# DRV8353FH_v0_7_Schematic.net
KiCad netlist of a schematic drawn in Altium Designer
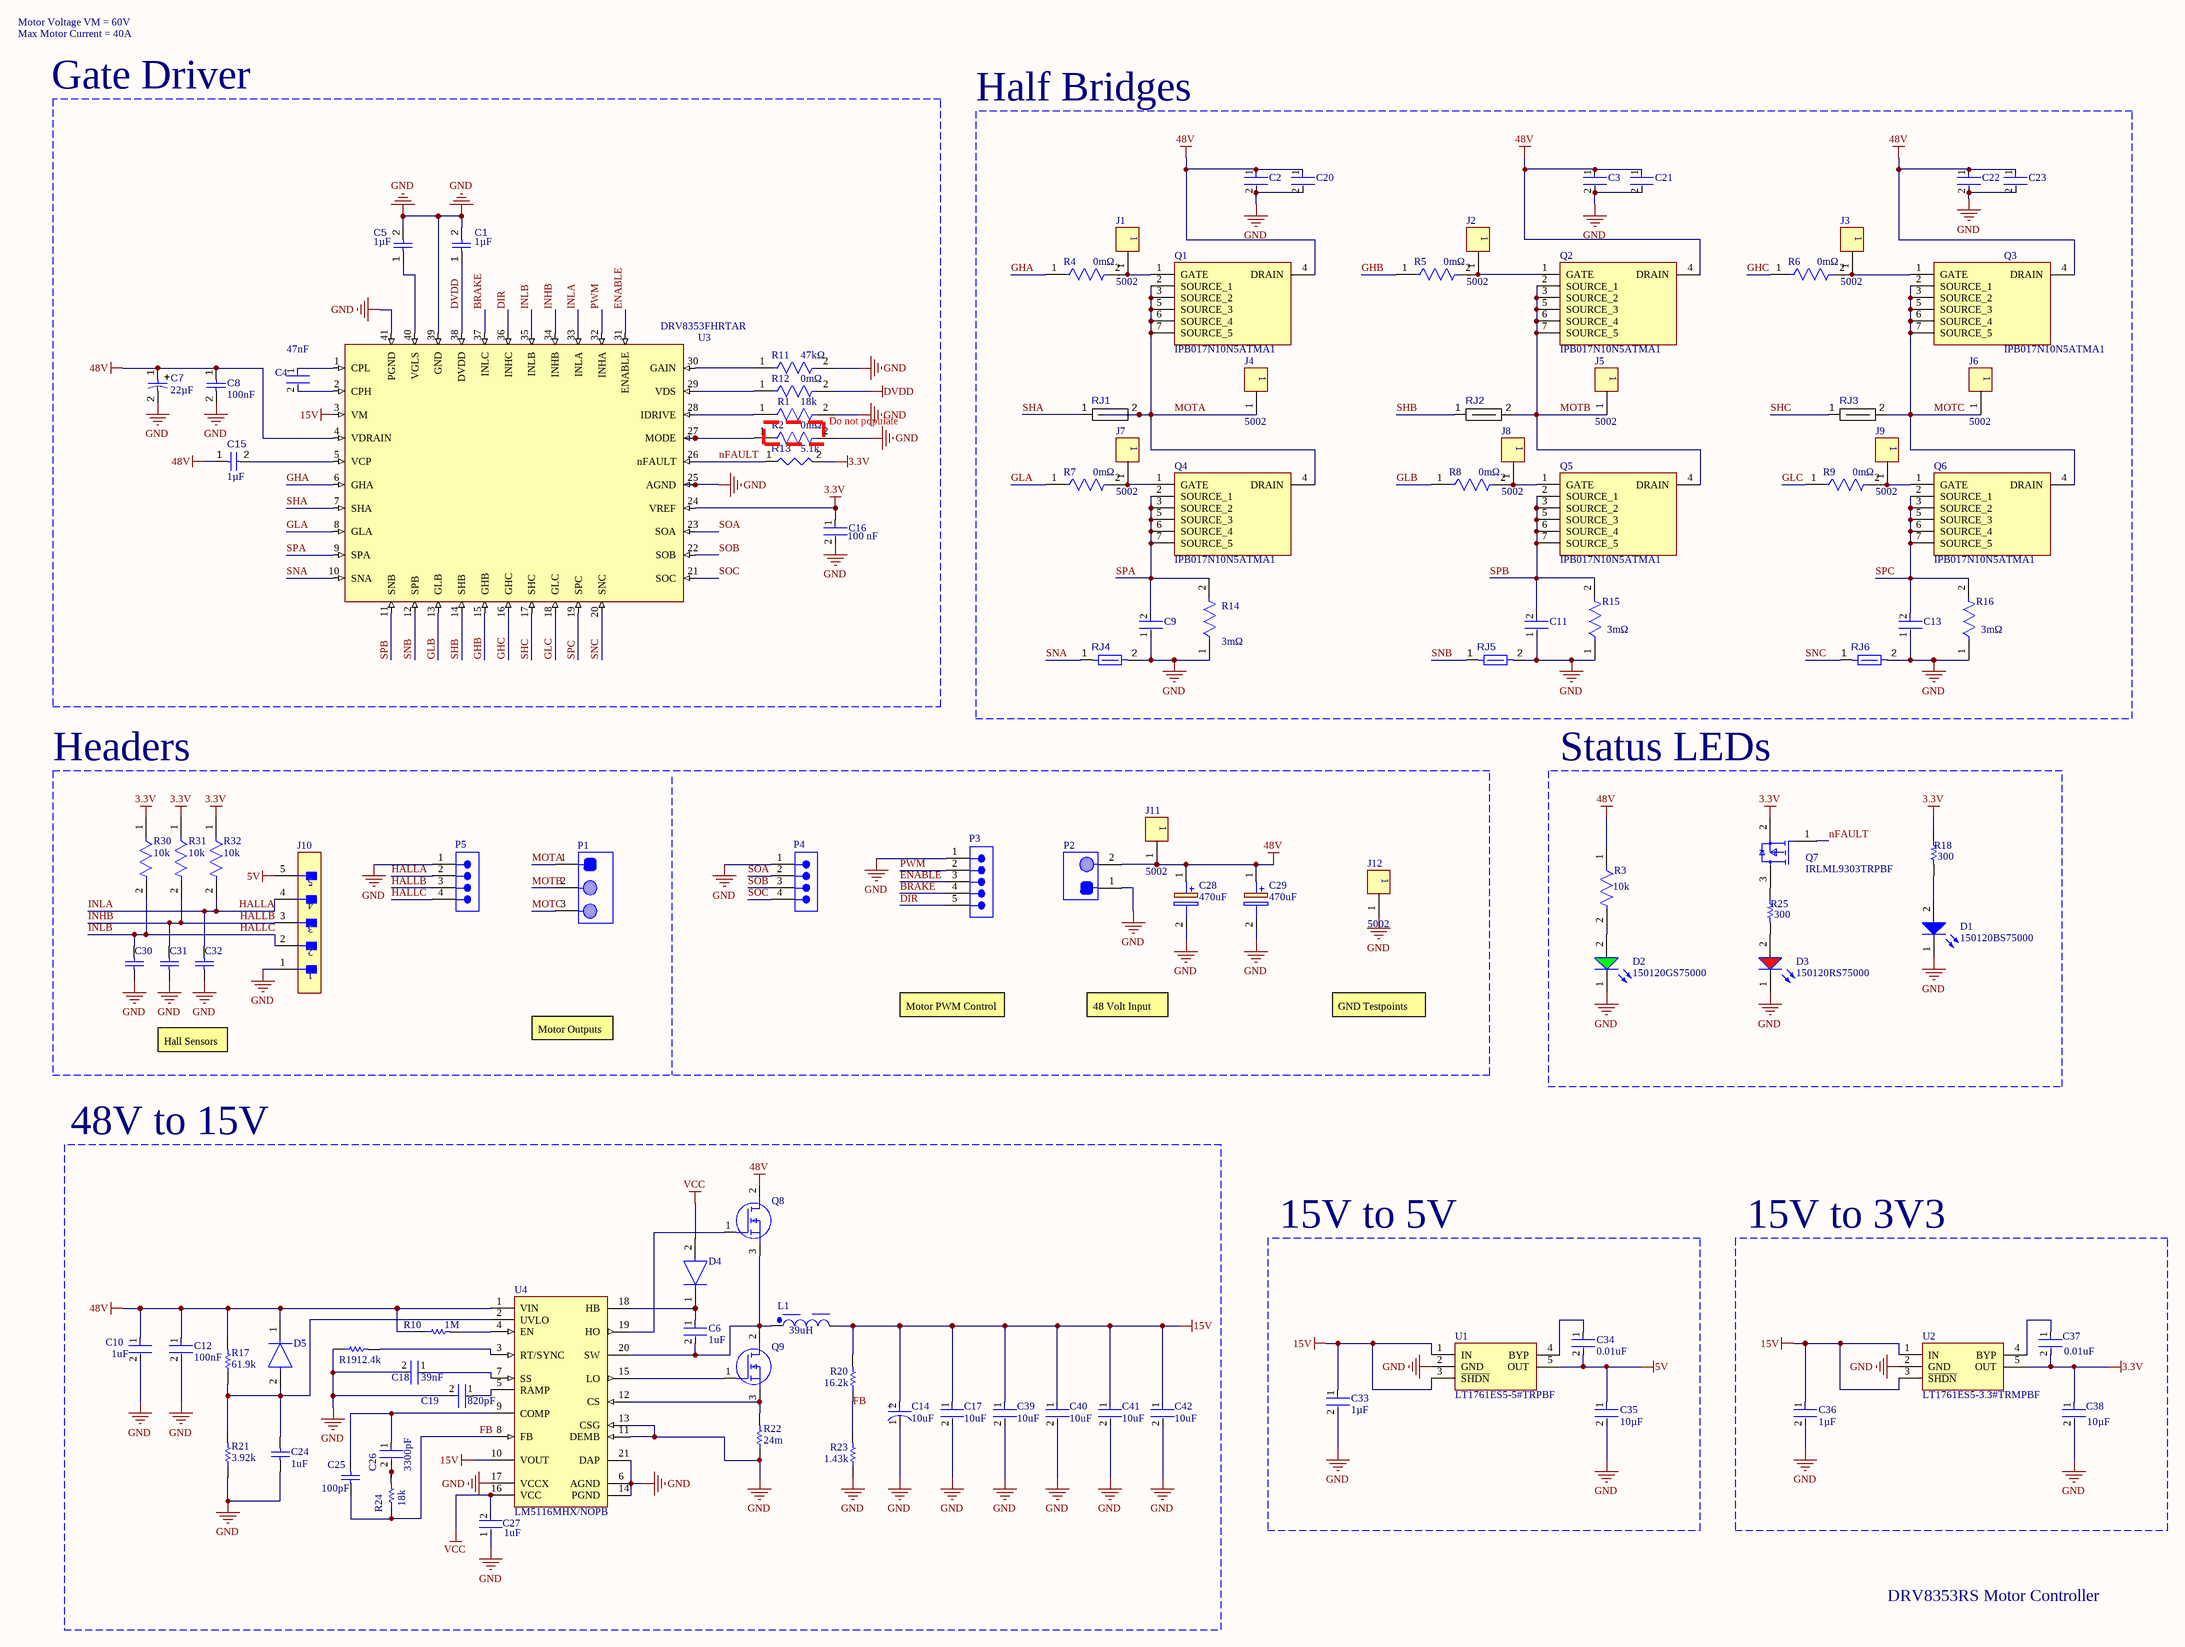
[diagram p0: DRV8353FH_v0.7_Schematic.SchDoc]

(export (version "E")
  (design (tool "Eeschema 10.0.6"))
  (components
    (comp (ref "C1")
      (value "1µF")
      (footprint "FP-CC0603-DA-IPC_B")
      (fields (field (name "Comment") "CC0603KRX5R8BB105"))
      (libsource (lib "CEV Electrical") (part "CAP-NP-2"))
    )
    (comp (ref "C2")
      (value "C1210C105K1RACTU")
      (footprint "FP-C1210C105K1RACTU-MFG")
      (description "CAP CER 1UF 100V X7R 1210")
      (fields (field (name "VOLTAGE") "100V") (field (name "TOLERANCE") "10%"))
      (libsource (lib "Altium Content Vault") (part "b4654b650e69147ec39a6b967a45e02"))
    )
    (comp (ref "C3")
      (value "C1210C105K1RACTU")
      (footprint "FP-C1210C105K1RACTU-MFG")
      (description "CAP CER 1UF 100V X7R 1210")
      (fields (field (name "VOLTAGE") "100V") (field (name "TOLERANCE") "10%"))
      (libsource (lib "Altium Content Vault") (part "b4654b650e69147ec39a6b967a45e02"))
    )
    (comp (ref "C4")
      (value "GCJ21BR72A473KA01L")
      (footprint "FP-GCJ21B-0_3-MFG")
      (description "Multilayer Ceramic Capacitors MLCC - SMD/SMT 0805 47000pF 10%, 100VDC,  X7R 15%")
      (fields (field (name "CAPACITANCE") "47nF") (field (name "TOLERANCE") "10%"))
      (libsource (lib "Altium Content Vault") (part "02cd4be3c70576c341d710602a673aa"))
    )
    (comp (ref "C5")
      (value "1µF")
      (footprint "FP-CC0603-DA-IPC_B")
      (fields (field (name "Comment") "CC0603KRX5R8BB105"))
      (libsource (lib "CEV Electrical") (part "CAP-NP-2"))
    )
    (comp (ref "C6")
      (value "1uF")
      (footprint "FP-CC0603-DA-MFG")
      (description "CAP CER 1UF 25V X5R 0603")
      (fields
        (field (name "OCTOPART") "https://octopart.com/cc0603krx5r8bb105-yageo-9292811")
        (field (name "MANUFACTURER") "YAGEO")
      )
      (libsource (lib "Altium Content Vault") (part "11868f565c42a9108669ba33697ecf6"))
    )
    (comp (ref "C7")
      (value "22µF")
      (footprint "CAPAE8983X105N")
      (fields (field (name "Comment") "UCD2A220MNL1GS"))
      (libsource (lib "") (part "CAP-NP-2_1"))
    )
    (comp (ref "C8")
      (value "100nF")
      (footprint "FP-CL10-IPC_B")
      (fields (field (name "Comment") "CL10B104KC8NNNC"))
      (libsource (lib "CEV Electrical") (part "CAP-NP-2"))
    )
    (comp (ref "C9")
      (value "C1608C0G2A102J080AA")
      (footprint "FP-C1608-080-0_1-MFG")
      (description "Multilayer Ceramic Capacitors 1nF ±5% 100V C0G SMD 0603")
      (fields (field (name "TOLERANCE") "5%"))
      (libsource (lib "Altium Content Vault") (part "236180d848d6139a670b325ea6854c9"))
    )
    (comp (ref "C10")
      (value "1uF")
      (footprint "FP-CL32-IPC_C")
      (description "Cap Ceramic 1uF 100V X7R ±10% SMD 1210 +125°C Embossed T/R")
      (fields (field (name "TOLERANCE") "10%") (field (name "VOLTAGE") "100V"))
      (libsource (lib "Altium Content Vault") (part "b4654b650e69147ec39a6b967a45e02"))
    )
    (comp (ref "C11")
      (value "C1608C0G2A102J080AA")
      (footprint "FP-C1608-080-0_1-MFG")
      (description "Multilayer Ceramic Capacitors 1nF ±5% 100V C0G SMD 0603")
      (fields (field (name "TOLERANCE") "5%"))
      (libsource (lib "Altium Content Vault") (part "236180d848d6139a670b325ea6854c9"))
    )
    (comp (ref "C12")
      (value "100nF")
      (footprint "FP-GRM188-0_1-e0_2_0_5-IPC_B")
      (description "Chip Multilayer Ceramic Capacitors for General Purpose, 0603, 0.10uF, X7R, 15%, 10%, 100V")
      (fields (field (name "VOLTAGE") "100V") (field (name "TOLERANCE") "10%"))
      (libsource (lib "Altium Content Vault") (part "11868f565c42a9108669ba33697ecf6"))
    )
    (comp (ref "C13")
      (value "C1608C0G2A102J080AA")
      (footprint "FP-C1608-080-0_1-MFG")
      (description "Multilayer Ceramic Capacitors 1nF ±5% 100V C0G SMD 0603")
      (fields (field (name "TOLERANCE") "5%"))
      (libsource (lib "Altium Content Vault") (part "236180d848d6139a670b325ea6854c9"))
    )
    (comp (ref "C14")
      (value "10uF")
      (footprint "FP-OS-CON-SMT-C6-MFG")
      (description "Conductive Polymer Aluminum Solid Capacitors (OS-CON) 10uF ±20% 50V")
      (fields (field (name "VOLTAGE") "50V") (field (name "TOLERANCE") "20%"))
      (libsource (lib "Altium Content Vault") (part "a00bbbee19879c290e62620ae7e47b1"))
    )
    (comp (ref "C15")
      (value "1µF")
      (footprint "FP-CC0603-DA-IPC_B")
      (fields (field (name "Comment") "CC0603KRX5R8BB105"))
      (libsource (lib "CEV Electrical") (part "CAP-NP-2"))
    )
    (comp (ref "C16")
      (value "100 nF")
      (footprint "FP-CC0603-DA-MFG")
      (description "CAP CER 0.1UF 16V X7R 0603")
      (fields
        (field (name "OCTOPART") "https://octopart.com/cc0603krx7r7bb104-yageo-192941")
        (field (name "TOLERANCE") "0.1")
      )
      (libsource (lib "Altium Content Vault") (part "11868f565c42a9108669ba33697ecf6"))
    )
    (comp (ref "C17")
      (value "10uF")
      (footprint "FP-CL31-IPC_C")
      (description "CAP CER 10UF 50V X5R 1206")
      (fields (field (name "TOLERANCE") "10%") (field (name "MANUFACTURER") "Samsung"))
      (libsource (lib "Altium Content Vault") (part "11868f565c42a9108669ba33697ecf6"))
    )
    (comp (ref "C18")
      (value "39nF")
      (footprint "FP-C0805C-DN-MFG")
      (description "C0805 39,000 pF U2J 30ppm/°C 1.00% 50 V")
      (fields
        (field (name "MANUFACTURER PART NUMBER") "C0805C393F5JACAUTO")
        (field (name "TOLERANCE") "0.01")
      )
      (libsource (lib "Altium Content Vault") (part "b4654b650e69147ec39a6b967a45e02"))
    )
    (comp (ref "C19")
      (value "820pF")
      (footprint "FP-C1608-080-0_1-IPC_C")
      (description "Multilayer Ceramic Capacitors 820pF ±5% 50V C0G SMD 0603")
      (fields (field (name "TOLERANCE") "5%"))
      (libsource (lib "Altium Content Vault") (part "236180d848d6139a670b325ea6854c9"))
    )
    (comp (ref "C20")
      (value "C1210C105K1RACTU")
      (footprint "FP-C1210C105K1RACTU-MFG")
      (description "CAP CER 1UF 100V X7R 1210")
      (fields (field (name "VOLTAGE") "100V") (field (name "TOLERANCE") "10%"))
      (libsource (lib "Altium Content Vault") (part "b4654b650e69147ec39a6b967a45e02"))
    )
    (comp (ref "C21")
      (value "C1210C105K1RACTU")
      (footprint "FP-C1210C105K1RACTU-MFG")
      (description "CAP CER 1UF 100V X7R 1210")
      (fields (field (name "VOLTAGE") "100V") (field (name "TOLERANCE") "10%"))
      (libsource (lib "Altium Content Vault") (part "b4654b650e69147ec39a6b967a45e02"))
    )
    (comp (ref "C22")
      (value "C1210C105K1RACTU")
      (footprint "FP-C1210C105K1RACTU-MFG")
      (description "CAP CER 1UF 100V X7R 1210")
      (fields (field (name "VOLTAGE") "100V") (field (name "TOLERANCE") "10%"))
      (libsource (lib "Altium Content Vault") (part "b4654b650e69147ec39a6b967a45e02"))
    )
    (comp (ref "C23")
      (value "C1210C105K1RACTU")
      (footprint "FP-C1210C105K1RACTU-MFG")
      (description "CAP CER 1UF 100V X7R 1210")
      (fields (field (name "VOLTAGE") "100V") (field (name "TOLERANCE") "10%"))
      (libsource (lib "Altium Content Vault") (part "b4654b650e69147ec39a6b967a45e02"))
    )
    (comp (ref "C24")
      (value "1uF")
      (footprint "CAPC2013X140X50ML20T25")
      (fields (field (name "MANUFACTURER") "Kemet") (field (name "PART NUMBER") "C0805C105K5RACTU"))
      (libsource (lib "Altium Content Vault") (part "CAP"))
    )
    (comp (ref "C25")
      (value "100pF")
      (footprint "CAPC1608X90X40ML10T20")
      (description "Chip Capacitor, 100 pF, +/- 5%, 50 V, -55 to 125 degC, 0603 (1608 Metric), RoHS, Tape and Reel")
      (fields (field (name "TOLERANCE") "5%") (field (name "VOLTAGE") "50V"))
      (libsource (lib "Altium Content Vault") (part "CAP-NP-2"))
    )
    (comp (ref "C26")
      (value "3300pF")
      (footprint "FP-C0603C-CF-MFG")
      (description "CAP CER 3300PF 50V 5% X7R 0603")
      (fields
        (field (name "MANUFACTURER PART NUMBER") "C0603C332J5RACTU")
        (field (name "MANUFACTURER") "KEMET")
      )
      (libsource (lib "Altium Content Vault") (part "b4654b650e69147ec39a6b967a45e02"))
    )
    (comp (ref "C27")
      (value "1uF")
      (footprint "FP-C1608-080-0_1-MFG")
      (description "Multilayer Ceramic Capacitors 1μF ±10% 35V X7R SMD 0603")
      (fields (field (name "TOLERANCE") "10%"))
      (libsource (lib "Altium Content Vault") (part "236180d848d6139a670b325ea6854c9"))
    )
    (comp (ref "C28")
      (value "470uF")
      (footprint "SamacSys:CAPPRD750W85D1800H4200")
      (description "Capacitor Polarised")
      (fields
        (field (name "MANUFACTURER_PART_NUMBER") "ECA-2CM471")
        (field (name "MOUSER PART NUMBER") "667-ECA-2CM471")
      )
      (libsource (lib "*") (part "ECA-2CM471"))
    )
    (comp (ref "C29")
      (value "470uF")
      (footprint "SamacSys:CAPPRD750W85D1800H4200")
      (description "Capacitor Polarised")
      (fields
        (field (name "MANUFACTURER_PART_NUMBER") "ECA-2CM471")
        (field (name "MOUSER PART NUMBER") "667-ECA-2CM471")
      )
      (libsource (lib "*") (part "ECA-2CM471"))
    )
    (comp (ref "C30")
      (value "VJ0603Y102KXACW1BC")
      (footprint "CAPC1608X95X40NL15T15")
      (fields (field (name "MANUFACTURER") "Vitramon"))
      (libsource (lib "Altium Content Vault") (part "CAP"))
    )
    (comp (ref "C31")
      (value "VJ0603Y102KXACW1BC")
      (footprint "CAPC1608X95X40NL15T15")
      (fields (field (name "MANUFACTURER") "Vitramon"))
      (libsource (lib "Altium Content Vault") (part "CAP"))
    )
    (comp (ref "C32")
      (value "VJ0603Y102KXACW1BC")
      (footprint "CAPC1608X95X40NL15T15")
      (fields (field (name "MANUFACTURER") "Vitramon"))
      (libsource (lib "Altium Content Vault") (part "CAP"))
    )
    (comp (ref "C33")
      (value "1µF")
      (footprint "FP-CC0603-DA-MFG")
      (description "CAP CER 1UF 25V X5R 0603")
      (fields
        (field (name "OCTOPART") "https://octopart.com/cc0603krx5r8bb105-yageo-9292811")
        (field (name "MANUFACTURER") "YAGEO")
      )
      (libsource (lib "Altium Content Vault") (part "11868f565c42a9108669ba33697ecf6"))
    )
    (comp (ref "C34")
      (value "0.01uF")
      (footprint "FP-CC0603-DA-MFG")
      (description "CAP CER 10000PF 25V X7R 0603")
      (fields (field (name "TOLERANCE") "0.1") (field (name "MANUFACTURER") "YAGEO"))
      (libsource (lib "Altium Content Vault") (part "11868f565c42a9108669ba33697ecf6"))
    )
    (comp (ref "C35")
      (value "10µF")
      (footprint "FP-CC0603-DC-IPC_A")
      (description "CAP CER 10UF 10V X5R 0603")
      (fields (field (name "TOLERANCE") "10%"))
      (libsource (lib "Altium Content Vault") (part "b4654b650e69147ec39a6b967a45e02"))
    )
    (comp (ref "C36")
      (value "1µF")
      (footprint "FP-CC0603-DA-MFG")
      (description "CAP CER 1UF 25V X5R 0603")
      (fields
        (field (name "OCTOPART") "https://octopart.com/cc0603krx5r8bb105-yageo-9292811")
        (field (name "MANUFACTURER") "YAGEO")
      )
      (libsource (lib "Altium Content Vault") (part "11868f565c42a9108669ba33697ecf6"))
    )
    (comp (ref "C37")
      (value "0.01uF")
      (footprint "FP-CC0603-DA-MFG")
      (description "CAP CER 10000PF 25V X7R 0603")
      (fields (field (name "TOLERANCE") "0.1") (field (name "MANUFACTURER") "YAGEO"))
      (libsource (lib "Altium Content Vault") (part "11868f565c42a9108669ba33697ecf6"))
    )
    (comp (ref "C38")
      (value "10µF")
      (footprint "FP-CC0603-DC-IPC_A")
      (description "CAP CER 10UF 10V X5R 0603")
      (fields (field (name "TOLERANCE") "10%"))
      (libsource (lib "Altium Content Vault") (part "b4654b650e69147ec39a6b967a45e02"))
    )
    (comp (ref "C39")
      (value "10uF")
      (footprint "FP-CL31-IPC_C")
      (description "CAP CER 10UF 50V X5R 1206")
      (fields (field (name "TOLERANCE") "10%") (field (name "MANUFACTURER") "Samsung"))
      (libsource (lib "Altium Content Vault") (part "11868f565c42a9108669ba33697ecf6"))
    )
    (comp (ref "C40")
      (value "10uF")
      (footprint "FP-CL31-IPC_C")
      (description "CAP CER 10UF 50V X5R 1206")
      (fields (field (name "TOLERANCE") "10%") (field (name "MANUFACTURER") "Samsung"))
      (libsource (lib "Altium Content Vault") (part "11868f565c42a9108669ba33697ecf6"))
    )
    (comp (ref "C41")
      (value "10uF")
      (footprint "FP-CL31-IPC_C")
      (description "CAP CER 10UF 50V X5R 1206")
      (fields (field (name "TOLERANCE") "10%") (field (name "MANUFACTURER") "Samsung"))
      (libsource (lib "Altium Content Vault") (part "11868f565c42a9108669ba33697ecf6"))
    )
    (comp (ref "C42")
      (value "10uF")
      (footprint "FP-CL31-IPC_C")
      (description "CAP CER 10UF 50V X5R 1206")
      (fields (field (name "TOLERANCE") "10%") (field (name "MANUFACTURER") "Samsung"))
      (libsource (lib "Altium Content Vault") (part "11868f565c42a9108669ba33697ecf6"))
    )
    (comp (ref "D1")
      (value "150120BS75000")
      (footprint "WL-SMCW_1206_150120xx75000")
      (description "WL-SMCW SMT Mono-Color Chip LED Waterclear")
      (libsource (lib "Altium Content Vault") (part "LED_Blue_2A-1K"))
    )
    (comp (ref "D2")
      (value "150120GS75000")
      (footprint "WL-SMCW_1206_150120xx75000")
      (description "WL-SMCW SMT Mono-Color Chip LED Waterclear")
      (libsource (lib "Altium Content Vault") (part "LED_Green_2A-1K"))
    )
    (comp (ref "D3")
      (value "150120RS75000")
      (footprint "WL-SMCW_1206_150120xx75000")
      (description "WL-SMCW SMT Mono-Color Chip LED Waterclear")
      (libsource (lib "Altium Content Vault") (part "LED_Red_2A-1K"))
    )
    (comp (ref "D4")
      (value "~")
      (footprint "FP-SOD523-MFG")
      (description "DIODE GEN PURP 100V 250MA SOD523")
      (libsource (lib "Altium Content Vault") (part "d7152d700b627762746794eb795d46e"))
    )
    (comp (ref "D5")
      (value "~")
      (footprint "FP-SOD523-MFG")
      (description "DIODE GEN PURP 100V 250MA SOD523")
      (libsource (lib "Altium Content Vault") (part "d7152d700b627762746794eb795d46e"))
    )
    (comp (ref "J1")
      (value "5002")
      (footprint "FP-5002-MFG")
      (description "PC TEST POINT MINIATURE WHITE")
      (libsource (lib "Altium Content Vault") (part "1e4615820a309e3ce90f9e6d957b7fa"))
    )
    (comp (ref "J2")
      (value "5002")
      (footprint "FP-5002-MFG")
      (description "PC TEST POINT MINIATURE WHITE")
      (libsource (lib "Altium Content Vault") (part "1e4615820a309e3ce90f9e6d957b7fa"))
    )
    (comp (ref "J3")
      (value "5002")
      (footprint "FP-5002-MFG")
      (description "PC TEST POINT MINIATURE WHITE")
      (libsource (lib "Altium Content Vault") (part "1e4615820a309e3ce90f9e6d957b7fa"))
    )
    (comp (ref "J4")
      (value "5002")
      (footprint "FP-5002-MFG")
      (description "PC TEST POINT MINIATURE WHITE")
      (libsource (lib "Altium Content Vault") (part "1e4615820a309e3ce90f9e6d957b7fa"))
    )
    (comp (ref "J5")
      (value "5002")
      (footprint "FP-5002-MFG")
      (description "PC TEST POINT MINIATURE WHITE")
      (libsource (lib "Altium Content Vault") (part "1e4615820a309e3ce90f9e6d957b7fa"))
    )
    (comp (ref "J6")
      (value "5002")
      (footprint "FP-5002-MFG")
      (description "PC TEST POINT MINIATURE WHITE")
      (libsource (lib "Altium Content Vault") (part "1e4615820a309e3ce90f9e6d957b7fa"))
    )
    (comp (ref "J7")
      (value "5002")
      (footprint "FP-5002-MFG")
      (description "PC TEST POINT MINIATURE WHITE")
      (libsource (lib "Altium Content Vault") (part "1e4615820a309e3ce90f9e6d957b7fa"))
    )
    (comp (ref "J8")
      (value "5002")
      (footprint "FP-5002-MFG")
      (description "PC TEST POINT MINIATURE WHITE")
      (libsource (lib "Altium Content Vault") (part "1e4615820a309e3ce90f9e6d957b7fa"))
    )
    (comp (ref "J9")
      (value "5002")
      (footprint "FP-5002-MFG")
      (description "PC TEST POINT MINIATURE WHITE")
      (libsource (lib "Altium Content Vault") (part "1e4615820a309e3ce90f9e6d957b7fa"))
    )
    (comp (ref "J10")
      (value "22-29-2051")
      (footprint "FP-22-29-2051-MFG")
      (description "2.54MM KK HDR VT FRICLK VRA .5AU")
      (libsource (lib "Altium Content Vault") (part "bf93c07fd2649a848d0ec8585582aab"))
    )
    (comp (ref "J11")
      (value "5002")
      (footprint "FP-5002-MFG")
      (description "PC TEST POINT MINIATURE WHITE")
      (libsource (lib "Altium Content Vault") (part "1e4615820a309e3ce90f9e6d957b7fa"))
    )
    (comp (ref "J12")
      (value "5002")
      (footprint "FP-5002-MFG")
      (description "PC TEST POINT MINIATURE WHITE")
      (libsource (lib "Altium Content Vault") (part "1e4615820a309e3ce90f9e6d957b7fa"))
    )
    (comp (ref "L1")
      (value "39uH")
      (footprint "WE-PD_1210")
      (fields (field (name "TOLERANCE") "20%"))
      (libsource (lib "Altium Content Vault") (part "Inductor - 2"))
    )
    (comp (ref "P1")
      (value "VP0365540000G")
      (footprint "VP0365540000G-Footprint-1")
      (description "VP10.16-3P slot screws Cr3 zinc, solder foot bright tin, steel stamping clamp")
      (libsource (lib "CEV Electrical") (part "VP0365540000G-Symbol-1"))
    )
    (comp (ref "P2")
      (value "VP0265540000G")
      (footprint "VP0265540000G-Footprint-1")
      (description "VP10.16-2P slot screws Cr3+ zinc, solder foot bright tin, steel stamping clamp")
      (libsource (lib "CEV Electrical") (part "VP0265540000G-Symbol-1"))
    )
    (comp (ref "P3")
      (value "~")
      (footprint "61300511121")
      (libsource (lib "Altium Content Vault") (part "Header_Male_1R_05P"))
    )
    (comp (ref "P4")
      (value "61300411121")
      (footprint "61300411121")
      (libsource (lib "Altium Content Vault") (part "Header_Male_1R_04P"))
    )
    (comp (ref "P5")
      (value "61300411121")
      (footprint "61300411121")
      (libsource (lib "Altium Content Vault") (part "Header_Male_1R_04P"))
    )
    (comp (ref "Q1")
      (value "IPB017N10N5ATMA1")
      (footprint "SamacSys:IPB017N10N5ATMA1")
      (description "MOSFET (N-Channel)")
      (fields (field (name "MOUSER PART NUMBER") "726-IPB017N10N5ATMA1"))
      (libsource (lib "*") (part "IPB017N10N5ATMA1"))
    )
    (comp (ref "Q2")
      (value "IPB017N10N5ATMA1")
      (footprint "SamacSys:IPB017N10N5ATMA1")
      (description "MOSFET (N-Channel)")
      (fields (field (name "MOUSER PART NUMBER") "726-IPB017N10N5ATMA1"))
      (libsource (lib "*") (part "IPB017N10N5ATMA1"))
    )
    (comp (ref "Q3")
      (value "IPB017N10N5ATMA1")
      (footprint "SamacSys:IPB017N10N5ATMA1")
      (description "MOSFET (N-Channel)")
      (fields (field (name "MOUSER PART NUMBER") "726-IPB017N10N5ATMA1"))
      (libsource (lib "*") (part "IPB017N10N5ATMA1"))
    )
    (comp (ref "Q4")
      (value "IPB017N10N5ATMA1")
      (footprint "SamacSys:IPB017N10N5ATMA1")
      (description "MOSFET (N-Channel)")
      (fields (field (name "MOUSER PART NUMBER") "726-IPB017N10N5ATMA1"))
      (libsource (lib "*") (part "IPB017N10N5ATMA1"))
    )
    (comp (ref "Q5")
      (value "IPB017N10N5ATMA1")
      (footprint "SamacSys:IPB017N10N5ATMA1")
      (description "MOSFET (N-Channel)")
      (fields (field (name "MOUSER PART NUMBER") "726-IPB017N10N5ATMA1"))
      (libsource (lib "*") (part "IPB017N10N5ATMA1"))
    )
    (comp (ref "Q6")
      (value "IPB017N10N5ATMA1")
      (footprint "SamacSys:IPB017N10N5ATMA1")
      (description "MOSFET (N-Channel)")
      (fields (field (name "MOUSER PART NUMBER") "726-IPB017N10N5ATMA1"))
      (libsource (lib "*") (part "IPB017N10N5ATMA1"))
    )
    (comp (ref "Q7")
      (value "IRLML9303TRPBF")
      (footprint "FP-Micro3-MFG")
      (description "MOSFET P-CH 30V 2.3A SOT-23-3")
      (fields
        (field (name "OCTOPART") "https://octopart.com/irlml9303trpbf-infineon-65874991")
        (field (name "MANUFACTURER") "Infineon")
      )
      (libsource (lib "Altium Content Vault") (part "8322ca5a1660585102f5f9fc075f3ed"))
    )
    (comp (ref "Q8")
      (value "~")
      (footprint "SamacSys:RD3P175SNFRATL")
      (description "MOSFET (N-Channel)")
      (fields
        (field (name "MANUFACTURER_PART_NUMBER") "RD3P100SNTL1")
        (field (name "MOUSER PART NUMBER") "755-RD3P100SNTL1")
      )
      (libsource (lib "*") (part "RD3P100SNTL1"))
    )
    (comp (ref "Q9")
      (value "~")
      (footprint "SamacSys:DMT10H009LK313")
      (description "MOSFET (N-Channel)")
      (fields
        (field (name "MANUFACTURER_PART_NUMBER") "DMT10H009LK3-13")
        (field (name "MOUSER PART NUMBER") "621-DMT10H009LK3-13")
      )
      (libsource (lib "*") (part "DMT10H009LK3-13"))
    )
    (comp (ref "R1")
      (value "18k")
      (footprint "FP-CRCW0603-e3-IPC_A")
      (description "RES Thick Film, 18kΩ, 1%, 0.1W, 100ppm/°C, 0603")
      (fields (field (name "TOLERANCE") "1%"))
      (libsource (lib "Altium Content Vault") (part "1029c3af85768c4190bb7ad29bc67b5"))
    )
    (comp (ref "R2")
      (value "RMCF0603ZT0R00")
      (footprint "FP-RMCF0603-MFG")
      (description "RES 0 OHM JUMPER 1/10W 0603")
      (fields
        (field (name "OCTOPART") "https://octopart.com/rmcf0603zt0r00-stackpole+electronics-19213618")
        (field (name "MANUFACTURER") "Stackpole")
        (field (name "RESISTANCE") "0mΩ")
      )
      (libsource (lib "Altium Content Vault") (part "1029c3af85768c4190bb7ad29bc67b5"))
    )
    (comp (ref "R3")
      (value "RK73H2BTTDD1002F")
      (footprint "FP-RK73H2B-IPC_C")
      (description "10kΩ ±1% 0.25W Chip Resistor 1206 Thick Film AEC-Q200 Qualified")
      (fields (field (name "RESISTANCE") "10k") (field (name "TOLERANCE") "1%"))
      (libsource (lib "Altium Content Vault") (part "1029c3af85768c4190bb7ad29bc67b5"))
    )
    (comp (ref "R4")
      (value "RMCF0603ZT0R00")
      (footprint "FP-RMCF0603-MFG")
      (description "RES 0 OHM JUMPER 1/10W 0603")
      (fields
        (field (name "OCTOPART") "https://octopart.com/rmcf0603zt0r00-stackpole+electronics-19213618")
        (field (name "MANUFACTURER") "Stackpole")
        (field (name "RESISTANCE") "0mΩ")
      )
      (libsource (lib "Altium Content Vault") (part "1029c3af85768c4190bb7ad29bc67b5"))
    )
    (comp (ref "R5")
      (value "RMCF0603ZT0R00")
      (footprint "FP-RMCF0603-MFG")
      (description "RES 0 OHM JUMPER 1/10W 0603")
      (fields
        (field (name "OCTOPART") "https://octopart.com/rmcf0603zt0r00-stackpole+electronics-19213618")
        (field (name "MANUFACTURER") "Stackpole")
        (field (name "RESISTANCE") "0mΩ")
      )
      (libsource (lib "Altium Content Vault") (part "1029c3af85768c4190bb7ad29bc67b5"))
    )
    (comp (ref "R6")
      (value "RMCF0603ZT0R00")
      (footprint "FP-RMCF0603-MFG")
      (description "RES 0 OHM JUMPER 1/10W 0603")
      (fields
        (field (name "OCTOPART") "https://octopart.com/rmcf0603zt0r00-stackpole+electronics-19213618")
        (field (name "MANUFACTURER") "Stackpole")
        (field (name "RESISTANCE") "0mΩ")
      )
      (libsource (lib "Altium Content Vault") (part "1029c3af85768c4190bb7ad29bc67b5"))
    )
    (comp (ref "R7")
      (value "RMCF0603ZT0R00")
      (footprint "FP-RMCF0603-MFG")
      (description "RES 0 OHM JUMPER 1/10W 0603")
      (fields
        (field (name "OCTOPART") "https://octopart.com/rmcf0603zt0r00-stackpole+electronics-19213618")
        (field (name "MANUFACTURER") "Stackpole")
        (field (name "RESISTANCE") "0mΩ")
      )
      (libsource (lib "Altium Content Vault") (part "1029c3af85768c4190bb7ad29bc67b5"))
    )
    (comp (ref "R8")
      (value "RMCF0603ZT0R00")
      (footprint "FP-RMCF0603-MFG")
      (description "RES 0 OHM JUMPER 1/10W 0603")
      (fields
        (field (name "OCTOPART") "https://octopart.com/rmcf0603zt0r00-stackpole+electronics-19213618")
        (field (name "MANUFACTURER") "Stackpole")
        (field (name "RESISTANCE") "0mΩ")
      )
      (libsource (lib "Altium Content Vault") (part "1029c3af85768c4190bb7ad29bc67b5"))
    )
    (comp (ref "R9")
      (value "RMCF0603ZT0R00")
      (footprint "FP-RMCF0603-MFG")
      (description "RES 0 OHM JUMPER 1/10W 0603")
      (fields
        (field (name "OCTOPART") "https://octopart.com/rmcf0603zt0r00-stackpole+electronics-19213618")
        (field (name "MANUFACTURER") "Stackpole")
        (field (name "RESISTANCE") "0mΩ")
      )
      (libsource (lib "Altium Content Vault") (part "1029c3af85768c4190bb7ad29bc67b5"))
    )
    (comp (ref "R10")
      (value "1M")
      (footprint "RESC1608X55X25LL10T15")
      (description "Chip Resistor, 1 MOhm, +/- 1%, 100 mW, -55 to 155 degC, 0603 (1608 Metric), RoHS, Tape and Reel")
      (fields (field (name "TOLERANCE") "20%"))
      (libsource (lib "Altium Content Vault") (part "RES-2"))
    )
    (comp (ref "R11")
      (value "ERA-3AEB473V")
      (footprint "FP-ERA3A-MFG")
      (fields (field (name "RESISTANCE") "47kΩ") (field (name "TOLERANCE") "0.1%"))
      (libsource (lib "Altium Content Vault") (part "8db39607336c341a927600551d01821"))
    )
    (comp (ref "R12")
      (value "RMCF0603ZT0R00")
      (footprint "FP-RMCF0603-MFG")
      (description "RES 0 OHM JUMPER 1/10W 0603")
      (fields
        (field (name "OCTOPART") "https://octopart.com/rmcf0603zt0r00-stackpole+electronics-19213618")
        (field (name "MANUFACTURER") "Stackpole")
        (field (name "RESISTANCE") "0mΩ")
      )
      (libsource (lib "Altium Content Vault") (part "1029c3af85768c4190bb7ad29bc67b5"))
    )
    (comp (ref "R13")
      (value "5.1k")
      (footprint "FP-ERJ3EK-IPC_A")
      (fields
        (field (name "TOLERANCE") "1%")
        (field (name "POWER") "100mW")
        (field (name "Comment") "ERJ-3EKF5101V")
      )
      (libsource (lib "CEV Electrical") (part "RES-2"))
    )
    (comp (ref "R14")
      (value "3mΩ")
      (footprint "FP-PU2512-0R003-MFG")
      (description "METAL SHUNT RESISTOR 2512 1% 75P")
      (fields (field (name "TOLERANCE") "1%") (field (name "MANUFACTURER") "Yageo"))
      (libsource (lib "Altium Content Vault") (part "1029c3af85768c4190bb7ad29bc67b5"))
    )
    (comp (ref "R15")
      (value "3mΩ")
      (footprint "FP-PU2512-0R003-MFG")
      (description "METAL SHUNT RESISTOR 2512 1% 75P")
      (fields (field (name "TOLERANCE") "1%") (field (name "MANUFACTURER") "Yageo"))
      (libsource (lib "Altium Content Vault") (part "1029c3af85768c4190bb7ad29bc67b5"))
    )
    (comp (ref "R16")
      (value "3mΩ")
      (footprint "FP-PU2512-0R003-MFG")
      (description "METAL SHUNT RESISTOR 2512 1% 75P")
      (fields (field (name "TOLERANCE") "1%") (field (name "MANUFACTURER") "Yageo"))
      (libsource (lib "Altium Content Vault") (part "1029c3af85768c4190bb7ad29bc67b5"))
    )
    (comp (ref "R17")
      (value "61.9k")
      (footprint "RESC1608X55X30ML15T15")
      (fields (field (name "MANUFACTURER") "Panasonic") (field (name "PART NUMBER") "ERJ-3EKF6192V"))
      (libsource (lib "Altium Content Vault") (part "RES"))
    )
    (comp (ref "R18")
      (value "300")
      (footprint "RESC1608X55X30LL20T20")
      (fields (field (name "PART NUMBER") "ERA3AEB301V") (field (name "MANUFACTURER") "Panasonic"))
      (libsource (lib "Altium Content Vault") (part "RES"))
    )
    (comp (ref "R19")
      (value "12.4k")
      (footprint "RESC2013X60X40NL20T25")
      (fields (field (name "MANUFACTURER") "Panasonic") (field (name "PART NUMBER") "ERA6AEB1242V"))
      (libsource (lib "Altium Content Vault") (part "RES"))
    )
    (comp (ref "R20")
      (value "16.2k")
      (footprint "RESC1608X55X25NL10T15")
      (fields (field (name "PART NUMBER") "RC0603FR-0716K2L") (field (name "MANUFACTURER") "Yageo"))
      (libsource (lib "Altium Content Vault") (part "RES"))
    )
    (comp (ref "R21")
      (value "3.92k")
      (footprint "RESC1608X55X30LL15T15")
      (fields (field (name "PART NUMBER") "ERJ-3EKF3921V") (field (name "MANUFACTURER") "Panasonic"))
      (libsource (lib "Altium Content Vault") (part "RES"))
    )
    (comp (ref "R22")
      (value "24m")
      (footprint "RESC3216X70X50NL05T20")
      (fields (field (name "PART NUMBER") "ERJ8CWFR024V") (field (name "MANUFACTURER") "Panasonic"))
      (libsource (lib "Altium Content Vault") (part "RES"))
    )
    (comp (ref "R23")
      (value "1.43k")
      (footprint "RESC1608X55X30ML15T15")
      (fields (field (name "MANUFACTURER") "Panasonic") (field (name "PART NUMBER") "ERJ-3EKF1431V"))
      (libsource (lib "Altium Content Vault") (part "RES"))
    )
    (comp (ref "R24")
      (value "18k")
      (footprint "RESC1608X55X30LL15T15")
      (fields (field (name "MANUFACTURER") "Panasonic") (field (name "PART NUMBER") "ERJ3EKF1802V"))
      (libsource (lib "") (part "RES-2_1"))
    )
    (comp (ref "R25")
      (value "300")
      (footprint "RESC1608X55X30LL20T20")
      (fields (field (name "PART NUMBER") "ERA3AEB301V") (field (name "MANUFACTURER") "Panasonic"))
      (libsource (lib "Altium Content Vault") (part "RES"))
    )
    (comp (ref "R30")
      (value "10k")
      (footprint "FP-RC0603-0_55-IPC_C")
      (description "RES 10K OHM 1% 1/10W 0603")
      (fields (field (name "TOLERANCE") "1%"))
      (libsource (lib "Altium Content Vault") (part "1029c3af85768c4190bb7ad29bc67b5"))
    )
    (comp (ref "R31")
      (value "10k")
      (footprint "FP-RC0603-0_55-IPC_C")
      (description "RES 10K OHM 1% 1/10W 0603")
      (fields (field (name "TOLERANCE") "1%"))
      (libsource (lib "Altium Content Vault") (part "1029c3af85768c4190bb7ad29bc67b5"))
    )
    (comp (ref "R32")
      (value "10k")
      (footprint "FP-RC0603-0_55-IPC_C")
      (description "RES 10K OHM 1% 1/10W 0603")
      (fields (field (name "TOLERANCE") "1%"))
      (libsource (lib "Altium Content Vault") (part "1029c3af85768c4190bb7ad29bc67b5"))
    )
    (comp (ref "RJ1")
      (value "Net Tie 30x70mil")
      (footprint "Net Tie 10x20mil-Footprint-1")
      (libsource (lib "CEV Electrical") (part "Net Tie"))
    )
    (comp (ref "RJ2")
      (value "Net Tie 30x70mil")
      (footprint "Net Tie 10x20mil-Footprint-1")
      (libsource (lib "CEV Electrical") (part "Net Tie"))
    )
    (comp (ref "RJ3")
      (value "Net Tie 30x70mil")
      (footprint "Net Tie 10x20mil-Footprint-1")
      (libsource (lib "CEV Electrical") (part "Net Tie"))
    )
    (comp (ref "RJ4")
      (value "Net Tie 12x30mil")
      (footprint "SHORT06-FP")
      (libsource (lib "CEV Electrical") (part "CMP-00022-00002-2"))
    )
    (comp (ref "RJ5")
      (value "Net Tie 12x30mil")
      (footprint "SHORT06-FP")
      (libsource (lib "CEV Electrical") (part "CMP-00022-00002-2"))
    )
    (comp (ref "RJ6")
      (value "Net Tie 12x30mil")
      (footprint "SHORT06-FP")
      (libsource (lib "CEV Electrical") (part "CMP-00022-00002-2"))
    )
    (comp (ref "U1")
      (value "LT1761ES5-5#TRPBF")
      (footprint "SamacSys:SOT95P280X90-5N")
      (description "Integrated Circuit")
      (fields (field (name "MOUSER PART NUMBER") "584-LT1761ES5-5TRPBF"))
      (libsource (lib "*") (part "LT1761ES5-5#TRPBF"))
    )
    (comp (ref "U2")
      (value "LT1761ES5-3.3#TRMPBF")
      (footprint "SamacSys:SOT95P280X100-5N")
      (description "Integrated Circuit")
      (fields (field (name "MOUSER PART NUMBER") "584-1761ES5-3.3TMPF"))
      (libsource (lib "*") (part "LT1761ES5-3.3#TRMPBF"))
    )
    (comp (ref "U3")
      (value "DRV8353FHRTAR")
      (footprint "QFN50P600X600X80_HS-41N")
      (description "Brushless DC Motor Controller, PQCC40")
      (libsource (lib "CEV Electrical") (part "DRV8353FHRTAR-Symbol-1"))
    )
    (comp (ref "U4")
      (value "LM5116MHX/NOPB")
      (footprint "PWP0020A_M")
      (description "Wide Range Synchronous Buck Controller, 20-pin TSSOP-EP, Pb-Free")
      (fields (field (name "MANUFACTURER") "Texas Instruments"))
      (libsource (lib "Altium Content Vault") (part "PM-REG-LM5116MH"))
    )
  )
  (nets
    (net (code "1") (name "/BRAKE") (class "Default")
      (node (ref "P3") (pin "4") (pinfunction "4_4") (pintype "passive"))
      (node (ref "U3") (pin "37") (pinfunction "INLC_37") (pintype "input"))
    )
    (net (code "2") (name "/DIR") (class "Default")
      (node (ref "P3") (pin "5") (pinfunction "5_5") (pintype "passive"))
      (node (ref "U3") (pin "36") (pinfunction "INHC_36") (pintype "input"))
    )
    (net (code "3") (name "/ENABLE") (class "Default")
      (node (ref "P3") (pin "3") (pinfunction "3_3") (pintype "passive"))
      (node (ref "U3") (pin "31") (pinfunction "ENABLE_31") (pintype "input"))
    )
    (net (code "4") (name "/FB") (class "Default")
      (node (ref "C25") (pin "1") (pinfunction "1_1") (pintype "passive"))
      (node (ref "R20") (pin "1") (pinfunction "1_1") (pintype "passive"))
      (node (ref "R23") (pin "2") (pinfunction "2_2") (pintype "passive"))
      (node (ref "R24") (pin "1") (pinfunction "1_1") (pintype "passive"))
      (node (ref "U4") (pin "8") (pinfunction "FB_8") (pintype "input"))
    )
    (net (code "5") (name "/GHA") (class "Default")
      (node (ref "R4") (pin "1") (pinfunction "1_1") (pintype "passive"))
      (node (ref "U3") (pin "6") (pinfunction "GHA_6") (pintype "input"))
    )
    (net (code "6") (name "/GHB") (class "Default")
      (node (ref "R5") (pin "1") (pinfunction "1_1") (pintype "passive"))
      (node (ref "U3") (pin "15") (pinfunction "GHB_15") (pintype "input"))
    )
    (net (code "7") (name "/GHC") (class "Default")
      (node (ref "R6") (pin "1") (pinfunction "1_1") (pintype "passive"))
      (node (ref "U3") (pin "16") (pinfunction "GHC_16") (pintype "input"))
    )
    (net (code "8") (name "/GLA") (class "Default")
      (node (ref "R7") (pin "1") (pinfunction "1_1") (pintype "passive"))
      (node (ref "U3") (pin "8") (pinfunction "GLA_8") (pintype "input"))
    )
    (net (code "9") (name "/GLB") (class "Default")
      (node (ref "R8") (pin "1") (pinfunction "1_1") (pintype "passive"))
      (node (ref "U3") (pin "13") (pinfunction "GLB_13") (pintype "input"))
    )
    (net (code "10") (name "/GLC") (class "Default")
      (node (ref "R9") (pin "1") (pinfunction "1_1") (pintype "passive"))
      (node (ref "U3") (pin "18") (pinfunction "GLC_18") (pintype "input"))
    )
    (net (code "11") (name "/HALLA") (class "Default")
      (node (ref "C32") (pin "2") (pinfunction "2_2") (pintype "passive"))
      (node (ref "J10") (pin "4") (pinfunction "4_4") (pintype "passive"))
      (node (ref "P5") (pin "2") (pinfunction "2_2") (pintype "passive"))
      (node (ref "R32") (pin "2") (pinfunction "2_2") (pintype "passive"))
      (node (ref "U3") (pin "33") (pinfunction "INLA_33") (pintype "input"))
    )
    (net (code "12") (name "/HALLB") (class "Default")
      (node (ref "C31") (pin "2") (pinfunction "2_2") (pintype "passive"))
      (node (ref "J10") (pin "3") (pinfunction "3_3") (pintype "passive"))
      (node (ref "P5") (pin "3") (pinfunction "3_3") (pintype "passive"))
      (node (ref "R31") (pin "2") (pinfunction "2_2") (pintype "passive"))
      (node (ref "U3") (pin "34") (pinfunction "INHB_34") (pintype "input"))
    )
    (net (code "13") (name "/HALLC") (class "Default")
      (node (ref "C30") (pin "2") (pinfunction "2_2") (pintype "passive"))
      (node (ref "J10") (pin "2") (pinfunction "2_2") (pintype "passive"))
      (node (ref "P5") (pin "4") (pinfunction "4_4") (pintype "passive"))
      (node (ref "R30") (pin "2") (pinfunction "2_2") (pintype "passive"))
      (node (ref "U3") (pin "35") (pinfunction "INLB_35") (pintype "input"))
    )
    (net (code "14") (name "/MOTA") (class "Default")
      (node (ref "J4") (pin "1") (pinfunction "1_1") (pintype "passive"))
      (node (ref "P1") (pin "1") (pinfunction "1_1") (pintype "passive"))
      (node (ref "Q1") (pin "2") (pinfunction "SOURCE_1_2") (pintype "passive"))
      (node (ref "Q1") (pin "3") (pinfunction "SOURCE_2_3") (pintype "passive"))
      (node (ref "Q1") (pin "5") (pinfunction "SOURCE_3_5") (pintype "passive"))
      (node (ref "Q1") (pin "6") (pinfunction "SOURCE_4_6") (pintype "passive"))
      (node (ref "Q1") (pin "7") (pinfunction "SOURCE_5_7") (pintype "passive"))
      (node (ref "Q4") (pin "4") (pinfunction "DRAIN_4") (pintype "passive"))
      (node (ref "RJ1") (pin "2") (pinfunction "2_2") (pintype "passive"))
    )
    (net (code "15") (name "/MOTB") (class "Default")
      (node (ref "J5") (pin "1") (pinfunction "1_1") (pintype "passive"))
      (node (ref "P1") (pin "2") (pinfunction "2_2") (pintype "passive"))
      (node (ref "Q2") (pin "2") (pinfunction "SOURCE_1_2") (pintype "passive"))
      (node (ref "Q2") (pin "3") (pinfunction "SOURCE_2_3") (pintype "passive"))
      (node (ref "Q2") (pin "5") (pinfunction "SOURCE_3_5") (pintype "passive"))
      (node (ref "Q2") (pin "6") (pinfunction "SOURCE_4_6") (pintype "passive"))
      (node (ref "Q2") (pin "7") (pinfunction "SOURCE_5_7") (pintype "passive"))
      (node (ref "Q5") (pin "4") (pinfunction "DRAIN_4") (pintype "passive"))
      (node (ref "RJ2") (pin "2") (pinfunction "2_2") (pintype "passive"))
    )
    (net (code "16") (name "/MOTC") (class "Default")
      (node (ref "J6") (pin "1") (pinfunction "1_1") (pintype "passive"))
      (node (ref "P1") (pin "3") (pinfunction "3_3") (pintype "passive"))
      (node (ref "Q3") (pin "2") (pinfunction "SOURCE_1_2") (pintype "passive"))
      (node (ref "Q3") (pin "3") (pinfunction "SOURCE_2_3") (pintype "passive"))
      (node (ref "Q3") (pin "5") (pinfunction "SOURCE_3_5") (pintype "passive"))
      (node (ref "Q3") (pin "6") (pinfunction "SOURCE_4_6") (pintype "passive"))
      (node (ref "Q3") (pin "7") (pinfunction "SOURCE_5_7") (pintype "passive"))
      (node (ref "Q6") (pin "4") (pinfunction "DRAIN_4") (pintype "passive"))
      (node (ref "RJ3") (pin "2") (pinfunction "2_2") (pintype "passive"))
    )
    (net (code "17") (name "/PWM") (class "Default")
      (node (ref "P3") (pin "2") (pinfunction "2_2") (pintype "passive"))
      (node (ref "U3") (pin "32") (pinfunction "INHA_32") (pintype "input"))
    )
    (net (code "18") (name "/SHA") (class "Default")
      (node (ref "RJ1") (pin "1") (pinfunction "1_1") (pintype "passive"))
      (node (ref "U3") (pin "7") (pinfunction "SHA_7") (pintype "input"))
    )
    (net (code "19") (name "/SHB") (class "Default")
      (node (ref "RJ2") (pin "1") (pinfunction "1_1") (pintype "passive"))
      (node (ref "U3") (pin "14") (pinfunction "SHB_14") (pintype "input"))
    )
    (net (code "20") (name "/SHC") (class "Default")
      (node (ref "RJ3") (pin "1") (pinfunction "1_1") (pintype "passive"))
      (node (ref "U3") (pin "17") (pinfunction "SHC_17") (pintype "input"))
    )
    (net (code "21") (name "/SNA") (class "Default")
      (node (ref "RJ4") (pin "1") (pinfunction "1_1") (pintype "passive"))
      (node (ref "U3") (pin "10") (pinfunction "SNA_10") (pintype "input"))
    )
    (net (code "22") (name "/SNB") (class "Default")
      (node (ref "RJ5") (pin "1") (pinfunction "1_1") (pintype "passive"))
      (node (ref "U3") (pin "12") (pinfunction "SPB_12") (pintype "input"))
    )
    (net (code "23") (name "/SNC") (class "Default")
      (node (ref "RJ6") (pin "1") (pinfunction "1_1") (pintype "passive"))
      (node (ref "U3") (pin "20") (pinfunction "SNC_20") (pintype "input"))
    )
    (net (code "24") (name "/SOA") (class "Default")
      (node (ref "P4") (pin "2") (pinfunction "2_2") (pintype "passive"))
      (node (ref "U3") (pin "23") (pinfunction "SOA_23") (pintype "input"))
    )
    (net (code "25") (name "/SOB") (class "Default")
      (node (ref "P4") (pin "3") (pinfunction "3_3") (pintype "passive"))
      (node (ref "U3") (pin "22") (pinfunction "SOB_22") (pintype "input"))
    )
    (net (code "26") (name "/SOC") (class "Default")
      (node (ref "P4") (pin "4") (pinfunction "4_4") (pintype "passive"))
      (node (ref "U3") (pin "21") (pinfunction "SOC_21") (pintype "input"))
    )
    (net (code "27") (name "/SPA") (class "Default")
      (node (ref "C9") (pin "2") (pinfunction "2_2") (pintype "passive"))
      (node (ref "Q4") (pin "2") (pinfunction "SOURCE_1_2") (pintype "passive"))
      (node (ref "Q4") (pin "3") (pinfunction "SOURCE_2_3") (pintype "passive"))
      (node (ref "Q4") (pin "5") (pinfunction "SOURCE_3_5") (pintype "passive"))
      (node (ref "Q4") (pin "6") (pinfunction "SOURCE_4_6") (pintype "passive"))
      (node (ref "Q4") (pin "7") (pinfunction "SOURCE_5_7") (pintype "passive"))
      (node (ref "R14") (pin "2") (pinfunction "2_2") (pintype "passive"))
      (node (ref "U3") (pin "9") (pinfunction "SPA_9") (pintype "input"))
    )
    (net (code "28") (name "/SPB") (class "Default")
      (node (ref "C11") (pin "2") (pinfunction "2_2") (pintype "passive"))
      (node (ref "Q5") (pin "2") (pinfunction "SOURCE_1_2") (pintype "passive"))
      (node (ref "Q5") (pin "3") (pinfunction "SOURCE_2_3") (pintype "passive"))
      (node (ref "Q5") (pin "5") (pinfunction "SOURCE_3_5") (pintype "passive"))
      (node (ref "Q5") (pin "6") (pinfunction "SOURCE_4_6") (pintype "passive"))
      (node (ref "Q5") (pin "7") (pinfunction "SOURCE_5_7") (pintype "passive"))
      (node (ref "R15") (pin "2") (pinfunction "2_2") (pintype "passive"))
      (node (ref "U3") (pin "11") (pinfunction "SNB_11") (pintype "input"))
    )
    (net (code "29") (name "/SPC") (class "Default")
      (node (ref "C13") (pin "2") (pinfunction "2_2") (pintype "passive"))
      (node (ref "Q6") (pin "2") (pinfunction "SOURCE_1_2") (pintype "passive"))
      (node (ref "Q6") (pin "3") (pinfunction "SOURCE_2_3") (pintype "passive"))
      (node (ref "Q6") (pin "5") (pinfunction "SOURCE_3_5") (pintype "passive"))
      (node (ref "Q6") (pin "6") (pinfunction "SOURCE_4_6") (pintype "passive"))
      (node (ref "Q6") (pin "7") (pinfunction "SOURCE_5_7") (pintype "passive"))
      (node (ref "R16") (pin "2") (pinfunction "2_2") (pintype "passive"))
      (node (ref "U3") (pin "19") (pinfunction "SPC_19") (pintype "input"))
    )
    (net (code "30") (name "/nFAULT") (class "Default")
      (node (ref "Q7") (pin "1") (pinfunction "G_1") (pintype "passive"))
      (node (ref "R13") (pin "1") (pinfunction "1_1") (pintype "passive"))
      (node (ref "U3") (pin "26") (pinfunction "nFAULT_26") (pintype "input"))
    )
    (net (code "31") (name "3.3V") (class "Default")
      (node (ref "C16") (pin "1") (pinfunction "1_1") (pintype "passive"))
      (node (ref "C37") (pin "2") (pinfunction "2_2") (pintype "passive"))
      (node (ref "C38") (pin "1") (pinfunction "1_1") (pintype "passive"))
      (node (ref "Q7") (pin "2") (pinfunction "S_2") (pintype "passive"))
      (node (ref "R13") (pin "2") (pinfunction "2_2") (pintype "passive"))
      (node (ref "R18") (pin "1") (pinfunction "1_1") (pintype "passive"))
      (node (ref "R30") (pin "1") (pinfunction "1_1") (pintype "passive"))
      (node (ref "R31") (pin "1") (pinfunction "1_1") (pintype "passive"))
      (node (ref "R32") (pin "1") (pinfunction "1_1") (pintype "passive"))
      (node (ref "U2") (pin "5") (pinfunction "OUT_5") (pintype "passive"))
      (node (ref "U3") (pin "24") (pinfunction "VREF_24") (pintype "input"))
    )
    (net (code "32") (name "5V") (class "Default")
      (node (ref "C34") (pin "2") (pinfunction "2_2") (pintype "passive"))
      (node (ref "C35") (pin "1") (pinfunction "1_1") (pintype "passive"))
      (node (ref "J10") (pin "5") (pinfunction "5_5") (pintype "passive"))
      (node (ref "U1") (pin "5") (pinfunction "OUT_5") (pintype "passive"))
    )
    (net (code "33") (name "15V") (class "Default")
      (node (ref "C14") (pin "2") (pinfunction "A_2") (pintype "passive"))
      (node (ref "C17") (pin "1") (pinfunction "1_1") (pintype "passive"))
      (node (ref "C33") (pin "1") (pinfunction "1_1") (pintype "passive"))
      (node (ref "C36") (pin "1") (pinfunction "1_1") (pintype "passive"))
      (node (ref "C39") (pin "1") (pinfunction "1_1") (pintype "passive"))
      (node (ref "C40") (pin "1") (pinfunction "1_1") (pintype "passive"))
      (node (ref "C41") (pin "1") (pinfunction "1_1") (pintype "passive"))
      (node (ref "C42") (pin "1") (pinfunction "1_1") (pintype "passive"))
      (node (ref "L1") (pin "2") (pinfunction "2_2") (pintype "passive"))
      (node (ref "R20") (pin "2") (pinfunction "2_2") (pintype "passive"))
      (node (ref "U1") (pin "1") (pinfunction "IN_1") (pintype "passive"))
      (node (ref "U1") (pin "3") (pinfunction "~{SHDN}_3") (pintype "passive"))
      (node (ref "U2") (pin "1") (pinfunction "IN_1") (pintype "passive"))
      (node (ref "U2") (pin "3") (pinfunction "~{SHDN}_3") (pintype "passive"))
      (node (ref "U3") (pin "3") (pinfunction "VM_3") (pintype "input"))
      (node (ref "U4") (pin "10") (pinfunction "VOUT_10") (pintype "passive"))
    )
    (net (code "34") (name "48V") (class "Default")
      (node (ref "C10") (pin "1") (pinfunction "1_1") (pintype "passive"))
      (node (ref "C12") (pin "1") (pinfunction "1_1") (pintype "passive"))
      (node (ref "C15") (pin "1") (pinfunction "1_1") (pintype "passive"))
      (node (ref "C2") (pin "1") (pinfunction "1_1") (pintype "passive"))
      (node (ref "C20") (pin "1") (pinfunction "1_1") (pintype "passive"))
      (node (ref "C21") (pin "1") (pinfunction "1_1") (pintype "passive"))
      (node (ref "C22") (pin "1") (pinfunction "1_1") (pintype "passive"))
      (node (ref "C23") (pin "1") (pinfunction "1_1") (pintype "passive"))
      (node (ref "C28") (pin "1") (pinfunction "+_1") (pintype "passive"))
      (node (ref "C29") (pin "1") (pinfunction "+_1") (pintype "passive"))
      (node (ref "C3") (pin "1") (pinfunction "1_1") (pintype "passive"))
      (node (ref "C7") (pin "1") (pinfunction "1_1") (pintype "passive"))
      (node (ref "C8") (pin "1") (pinfunction "1_1") (pintype "passive"))
      (node (ref "D5") (pin "1") (pinfunction "C_1") (pintype "passive"))
      (node (ref "J11") (pin "1") (pinfunction "1_1") (pintype "passive"))
      (node (ref "P2") (pin "2") (pinfunction "2_2") (pintype "passive"))
      (node (ref "Q1") (pin "4") (pinfunction "DRAIN_4") (pintype "passive"))
      (node (ref "Q2") (pin "4") (pinfunction "DRAIN_4") (pintype "passive"))
      (node (ref "Q3") (pin "4") (pinfunction "DRAIN_4") (pintype "passive"))
      (node (ref "Q8") (pin "2") (pinfunction "D_2") (pintype "passive"))
      (node (ref "R10") (pin "1") (pinfunction "1_1") (pintype "passive"))
      (node (ref "R17") (pin "2") (pinfunction "2_2") (pintype "passive"))
      (node (ref "R3") (pin "1") (pinfunction "1_1") (pintype "passive"))
      (node (ref "U3") (pin "4") (pinfunction "VDRAIN_4") (pintype "input"))
      (node (ref "U4") (pin "1") (pinfunction "VIN_1") (pintype "power_in"))
    )
    (net (code "35") (name "DVDD") (class "Default")
      (node (ref "C1") (pin "1") (pinfunction "1_1") (pintype "passive"))
      (node (ref "R12") (pin "2") (pinfunction "2_2") (pintype "passive"))
      (node (ref "U3") (pin "38") (pinfunction "DVDD_38") (pintype "input"))
    )
    (net (code "36") (name "GND") (class "Default")
      (node (ref "C1") (pin "2") (pinfunction "2_2") (pintype "passive"))
      (node (ref "C10") (pin "2") (pinfunction "2_2") (pintype "passive"))
      (node (ref "C11") (pin "1") (pinfunction "1_1") (pintype "passive"))
      (node (ref "C12") (pin "2") (pinfunction "2_2") (pintype "passive"))
      (node (ref "C13") (pin "1") (pinfunction "1_1") (pintype "passive"))
      (node (ref "C14") (pin "1") (pinfunction "C_1") (pintype "passive"))
      (node (ref "C16") (pin "2") (pinfunction "2_2") (pintype "passive"))
      (node (ref "C17") (pin "2") (pinfunction "2_2") (pintype "passive"))
      (node (ref "C18") (pin "2") (pinfunction "2_2") (pintype "passive"))
      (node (ref "C19") (pin "2") (pinfunction "2_2") (pintype "passive"))
      (node (ref "C2") (pin "2") (pinfunction "2_2") (pintype "passive"))
      (node (ref "C20") (pin "2") (pinfunction "2_2") (pintype "passive"))
      (node (ref "C21") (pin "2") (pinfunction "2_2") (pintype "passive"))
      (node (ref "C22") (pin "2") (pinfunction "2_2") (pintype "passive"))
      (node (ref "C23") (pin "2") (pinfunction "2_2") (pintype "passive"))
      (node (ref "C24") (pin "1") (pinfunction "1_1") (pintype "passive"))
      (node (ref "C27") (pin "1") (pinfunction "1_1") (pintype "passive"))
      (node (ref "C28") (pin "2") (pinfunction "-_2") (pintype "passive"))
      (node (ref "C29") (pin "2") (pinfunction "-_2") (pintype "passive"))
      (node (ref "C3") (pin "2") (pinfunction "2_2") (pintype "passive"))
      (node (ref "C30") (pin "1") (pinfunction "1_1") (pintype "passive"))
      (node (ref "C31") (pin "1") (pinfunction "1_1") (pintype "passive"))
      (node (ref "C32") (pin "1") (pinfunction "1_1") (pintype "passive"))
      (node (ref "C33") (pin "2") (pinfunction "2_2") (pintype "passive"))
      (node (ref "C35") (pin "2") (pinfunction "2_2") (pintype "passive"))
      (node (ref "C36") (pin "2") (pinfunction "2_2") (pintype "passive"))
      (node (ref "C38") (pin "2") (pinfunction "2_2") (pintype "passive"))
      (node (ref "C39") (pin "2") (pinfunction "2_2") (pintype "passive"))
      (node (ref "C40") (pin "2") (pinfunction "2_2") (pintype "passive"))
      (node (ref "C41") (pin "2") (pinfunction "2_2") (pintype "passive"))
      (node (ref "C42") (pin "2") (pinfunction "2_2") (pintype "passive"))
      (node (ref "C5") (pin "2") (pinfunction "2_2") (pintype "passive"))
      (node (ref "C7") (pin "2") (pinfunction "2_2") (pintype "passive"))
      (node (ref "C8") (pin "2") (pinfunction "2_2") (pintype "passive"))
      (node (ref "C9") (pin "1") (pinfunction "1_1") (pintype "passive"))
      (node (ref "D1") (pin "1") (pinfunction "K_1") (pintype "passive"))
      (node (ref "D2") (pin "1") (pinfunction "K_1") (pintype "passive"))
      (node (ref "D3") (pin "1") (pinfunction "K_1") (pintype "passive"))
      (node (ref "J10") (pin "1") (pinfunction "1_1") (pintype "passive"))
      (node (ref "J12") (pin "1") (pinfunction "1_1") (pintype "passive"))
      (node (ref "P2") (pin "1") (pinfunction "1_1") (pintype "passive"))
      (node (ref "P3") (pin "1") (pinfunction "1_1") (pintype "passive"))
      (node (ref "P4") (pin "1") (pinfunction "1_1") (pintype "passive"))
      (node (ref "P5") (pin "1") (pinfunction "1_1") (pintype "passive"))
      (node (ref "R1") (pin "2") (pinfunction "2_2") (pintype "passive"))
      (node (ref "R11") (pin "2") (pinfunction "2_2") (pintype "passive"))
      (node (ref "R14") (pin "1") (pinfunction "1_1") (pintype "passive"))
      (node (ref "R15") (pin "1") (pinfunction "1_1") (pintype "passive"))
      (node (ref "R16") (pin "1") (pinfunction "1_1") (pintype "passive"))
      (node (ref "R19") (pin "1") (pinfunction "1_1") (pintype "passive"))
      (node (ref "R2") (pin "2") (pinfunction "2_2") (pintype "passive"))
      (node (ref "R21") (pin "1") (pinfunction "1_1") (pintype "passive"))
      (node (ref "R22") (pin "1") (pinfunction "1_1") (pintype "passive"))
      (node (ref "R23") (pin "1") (pinfunction "1_1") (pintype "passive"))
      (node (ref "RJ4") (pin "2") (pinfunction "2_2") (pintype "passive"))
      (node (ref "RJ5") (pin "2") (pinfunction "2_2") (pintype "passive"))
      (node (ref "RJ6") (pin "2") (pinfunction "2_2") (pintype "passive"))
      (node (ref "U1") (pin "2") (pinfunction "GND_2") (pintype "passive"))
      (node (ref "U2") (pin "2") (pinfunction "GND_2") (pintype "passive"))
      (node (ref "U3") (pin "25") (pinfunction "AGND_25") (pintype "input"))
      (node (ref "U3") (pin "39") (pinfunction "GND_39") (pintype "input"))
      (node (ref "U3") (pin "41") (pinfunction "PGND_41") (pintype "input"))
      (node (ref "U4") (pin "11") (pinfunction "DEMB_11") (pintype "input"))
      (node (ref "U4") (pin "13") (pinfunction "CSG_13") (pintype "input"))
      (node (ref "U4") (pin "14") (pinfunction "PGND_14") (pintype "power_in"))
      (node (ref "U4") (pin "17") (pinfunction "VCCX_17") (pintype "power_in"))
      (node (ref "U4") (pin "21") (pinfunction "DAP_21") (pintype "power_in"))
      (node (ref "U4") (pin "6") (pinfunction "AGND_6") (pintype "power_in"))
    )
    (net (code "37") (name "Net-(C26-Pad2)") (class "Default")
      (node (ref "C26") (pin "2") (pinfunction "2_2") (pintype "passive"))
      (node (ref "R24") (pin "2") (pinfunction "2_2") (pintype "passive"))
    )
    (net (code "38") (name "Net-(D1-A)") (class "Default")
      (node (ref "D1") (pin "2") (pinfunction "A_2") (pintype "passive"))
      (node (ref "R18") (pin "2") (pinfunction "2_2") (pintype "passive"))
    )
    (net (code "39") (name "Net-(D2-A)") (class "Default")
      (node (ref "D2") (pin "2") (pinfunction "A_2") (pintype "passive"))
      (node (ref "R3") (pin "2") (pinfunction "2_2") (pintype "passive"))
    )
    (net (code "40") (name "Net-(D3-A)") (class "Default")
      (node (ref "D3") (pin "2") (pinfunction "A_2") (pintype "passive"))
      (node (ref "R25") (pin "2") (pinfunction "2_2") (pintype "passive"))
    )
    (net (code "41") (name "Net-(D4-C)") (class "Default")
      (node (ref "C6") (pin "1") (pinfunction "1_1") (pintype "passive"))
      (node (ref "D4") (pin "1") (pinfunction "C_1") (pintype "passive"))
      (node (ref "U4") (pin "18") (pinfunction "HB_18") (pintype "passive"))
    )
    (net (code "42") (name "Net-(D5-A)") (class "Default")
      (node (ref "C24") (pin "2") (pinfunction "2_2") (pintype "passive"))
      (node (ref "D5") (pin "2") (pinfunction "A_2") (pintype "passive"))
      (node (ref "R17") (pin "1") (pinfunction "1_1") (pintype "passive"))
      (node (ref "R21") (pin "2") (pinfunction "2_2") (pintype "passive"))
      (node (ref "U4") (pin "2") (pinfunction "UVLO_2") (pintype "passive"))
    )
    (net (code "43") (name "Net-(Q1-GATE)") (class "Default")
      (node (ref "J1") (pin "1") (pinfunction "1_1") (pintype "passive"))
      (node (ref "Q1") (pin "1") (pinfunction "GATE_1") (pintype "passive"))
      (node (ref "R4") (pin "2") (pinfunction "2_2") (pintype "passive"))
    )
    (net (code "44") (name "Net-(Q2-GATE)") (class "Default")
      (node (ref "J2") (pin "1") (pinfunction "1_1") (pintype "passive"))
      (node (ref "Q2") (pin "1") (pinfunction "GATE_1") (pintype "passive"))
      (node (ref "R5") (pin "2") (pinfunction "2_2") (pintype "passive"))
    )
    (net (code "45") (name "Net-(Q3-GATE)") (class "Default")
      (node (ref "J3") (pin "1") (pinfunction "1_1") (pintype "passive"))
      (node (ref "Q3") (pin "1") (pinfunction "GATE_1") (pintype "passive"))
      (node (ref "R6") (pin "2") (pinfunction "2_2") (pintype "passive"))
    )
    (net (code "46") (name "Net-(Q4-GATE)") (class "Default")
      (node (ref "J7") (pin "1") (pinfunction "1_1") (pintype "passive"))
      (node (ref "Q4") (pin "1") (pinfunction "GATE_1") (pintype "passive"))
      (node (ref "R7") (pin "2") (pinfunction "2_2") (pintype "passive"))
    )
    (net (code "47") (name "Net-(Q5-GATE)") (class "Default")
      (node (ref "J8") (pin "1") (pinfunction "1_1") (pintype "passive"))
      (node (ref "Q5") (pin "1") (pinfunction "GATE_1") (pintype "passive"))
      (node (ref "R8") (pin "2") (pinfunction "2_2") (pintype "passive"))
    )
    (net (code "48") (name "Net-(Q6-GATE)") (class "Default")
      (node (ref "J9") (pin "1") (pinfunction "1_1") (pintype "passive"))
      (node (ref "Q6") (pin "1") (pinfunction "GATE_1") (pintype "passive"))
      (node (ref "R9") (pin "2") (pinfunction "2_2") (pintype "passive"))
    )
    (net (code "49") (name "Net-(Q7-D)") (class "Default")
      (node (ref "Q7") (pin "3") (pinfunction "D_3") (pintype "passive"))
      (node (ref "R25") (pin "1") (pinfunction "1_1") (pintype "passive"))
    )
    (net (code "50") (name "Net-(Q8-G)") (class "Default")
      (node (ref "Q8") (pin "1") (pinfunction "G_1") (pintype "passive"))
      (node (ref "U4") (pin "19") (pinfunction "HO_19") (pintype "output"))
    )
    (net (code "51") (name "Net-(Q8-S)") (class "Default")
      (node (ref "C6") (pin "2") (pinfunction "2_2") (pintype "passive"))
      (node (ref "L1") (pin "1") (pinfunction "1_1") (pintype "passive"))
      (node (ref "Q8") (pin "3") (pinfunction "S_3") (pintype "passive"))
      (node (ref "Q9") (pin "2") (pinfunction "D_2") (pintype "passive"))
      (node (ref "U4") (pin "20") (pinfunction "SW_20") (pintype "power_in"))
    )
    (net (code "52") (name "Net-(Q9-G)") (class "Default")
      (node (ref "Q9") (pin "1") (pinfunction "G_1") (pintype "passive"))
      (node (ref "U4") (pin "15") (pinfunction "LO_15") (pintype "output"))
    )
    (net (code "53") (name "Net-(Q9-S)") (class "Default")
      (node (ref "Q9") (pin "3") (pinfunction "S_3") (pintype "passive"))
      (node (ref "R22") (pin "2") (pinfunction "2_2") (pintype "passive"))
      (node (ref "U4") (pin "12") (pinfunction "CS_12") (pintype "input"))
    )
    (net (code "54") (name "Net-(U1-BYP)") (class "Default")
      (node (ref "C34") (pin "1") (pinfunction "1_1") (pintype "passive"))
      (node (ref "U1") (pin "4") (pinfunction "BYP_4") (pintype "passive"))
    )
    (net (code "55") (name "Net-(U2-BYP)") (class "Default")
      (node (ref "C37") (pin "1") (pinfunction "1_1") (pintype "passive"))
      (node (ref "U2") (pin "4") (pinfunction "BYP_4") (pintype "passive"))
    )
    (net (code "56") (name "Net-(U3-CPH)") (class "Default")
      (node (ref "C4") (pin "2") (pinfunction "2_2") (pintype "passive"))
      (node (ref "U3") (pin "2") (pinfunction "CPH_2") (pintype "input"))
    )
    (net (code "57") (name "Net-(U3-CPL)") (class "Default")
      (node (ref "C4") (pin "1") (pinfunction "1_1") (pintype "passive"))
      (node (ref "U3") (pin "1") (pinfunction "CPL_1") (pintype "input"))
    )
    (net (code "58") (name "Net-(U3-GAIN)") (class "Default")
      (node (ref "R11") (pin "1") (pinfunction "1_1") (pintype "passive"))
      (node (ref "U3") (pin "30") (pinfunction "GAIN_30") (pintype "input"))
    )
    (net (code "59") (name "Net-(U3-IDRIVE)") (class "Default")
      (node (ref "R1") (pin "1") (pinfunction "1_1") (pintype "passive"))
      (node (ref "U3") (pin "28") (pinfunction "IDRIVE_28") (pintype "input"))
    )
    (net (code "60") (name "Net-(U3-MODE)") (class "Default")
      (node (ref "R2") (pin "1") (pinfunction "1_1") (pintype "passive"))
      (node (ref "U3") (pin "27") (pinfunction "MODE_27") (pintype "input"))
    )
    (net (code "61") (name "Net-(U3-VCP)") (class "Default")
      (node (ref "C15") (pin "2") (pinfunction "2_2") (pintype "passive"))
      (node (ref "U3") (pin "5") (pinfunction "VCP_5") (pintype "input"))
    )
    (net (code "62") (name "Net-(U3-VDS)") (class "Default")
      (node (ref "R12") (pin "1") (pinfunction "1_1") (pintype "passive"))
      (node (ref "U3") (pin "29") (pinfunction "VDS_29") (pintype "input"))
    )
    (net (code "63") (name "Net-(U3-VGLS)") (class "Default")
      (node (ref "C5") (pin "1") (pinfunction "1_1") (pintype "passive"))
      (node (ref "U3") (pin "40") (pinfunction "VGLS_40") (pintype "input"))
    )
    (net (code "64") (name "Net-(U4-COMP)") (class "Default")
      (node (ref "C25") (pin "2") (pinfunction "2_2") (pintype "passive"))
      (node (ref "C26") (pin "1") (pinfunction "1_1") (pintype "passive"))
      (node (ref "U4") (pin "9") (pinfunction "COMP_9") (pintype "passive"))
    )
    (net (code "65") (name "Net-(U4-EN)") (class "Default")
      (node (ref "R10") (pin "2") (pinfunction "2_2") (pintype "passive"))
      (node (ref "U4") (pin "4") (pinfunction "EN_4") (pintype "input"))
    )
    (net (code "66") (name "Net-(U4-RAMP)") (class "Default")
      (node (ref "C19") (pin "1") (pinfunction "1_1") (pintype "passive"))
      (node (ref "U4") (pin "5") (pinfunction "RAMP_5") (pintype "passive"))
    )
    (net (code "67") (name "Net-(U4-RT{slash}SYNC)") (class "Default")
      (node (ref "R19") (pin "2") (pinfunction "2_2") (pintype "passive"))
      (node (ref "U4") (pin "3") (pinfunction "RT/SYNC_3") (pintype "input"))
    )
    (net (code "68") (name "Net-(U4-SS)") (class "Default")
      (node (ref "C18") (pin "1") (pinfunction "1_1") (pintype "passive"))
      (node (ref "U4") (pin "7") (pinfunction "SS_7") (pintype "input"))
    )
    (net (code "69") (name "VCC") (class "Default")
      (node (ref "C27") (pin "2") (pinfunction "2_2") (pintype "passive"))
      (node (ref "D4") (pin "2") (pinfunction "A_2") (pintype "passive"))
      (node (ref "U4") (pin "16") (pinfunction "VCC_16") (pintype "power_in"))
    )
  )
)
